# LTC3105_Charger.net
KiCad netlist of a schematic drawn in EAGLE
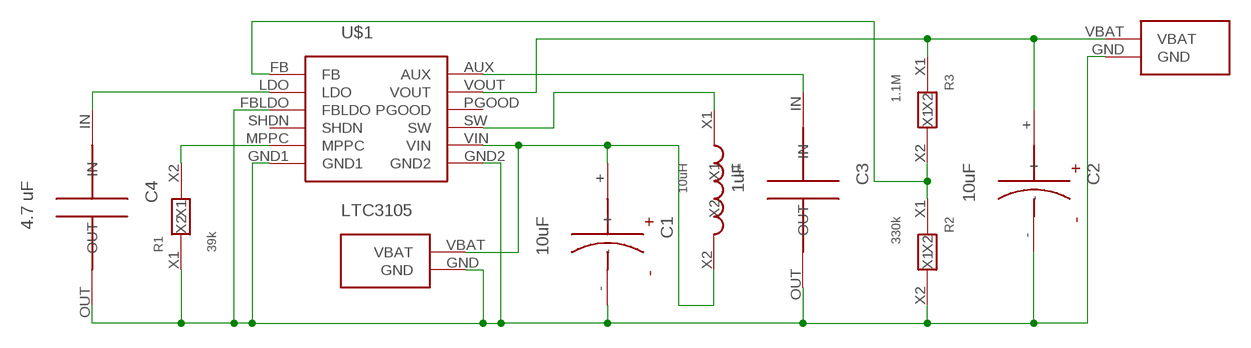
[diagram p0: schematic, sheet 1]

(export (version "E")
  (design (tool "Eeschema 10.0.6"))
  (components
    (comp (ref "C1")
      (value "10uF")
      (footprint "eagle-import:C_ELT_2MM")
      (libsource (lib "eagle-import") (part "C_ELT_2MM"))
    )
    (comp (ref "C2")
      (value "10uF")
      (footprint "eagle-import:C_ELT_2MM")
      (libsource (lib "eagle-import") (part "C_ELT_2MM"))
    )
    (comp (ref "C3")
      (value "1uF")
      (footprint "eagle-import:C_CER_5MM")
      (libsource (lib "eagle-import") (part "C_CER_5MM"))
    )
    (comp (ref "C4")
      (value "4.7 uF")
      (footprint "eagle-import:C_CER_5MM")
      (libsource (lib "eagle-import") (part "C_CER_5MM"))
    )
    (comp (ref "L1")
      (value "10uH")
      (footprint "eagle-import:L_10X3")
      (libsource (lib "eagle-import") (part "L_10X3"))
    )
    (comp (ref "R1")
      (value "39k")
      (footprint "eagle-import:R_6X2")
      (libsource (lib "eagle-import") (part "R_6X2"))
    )
    (comp (ref "R2")
      (value "330k")
      (footprint "eagle-import:R_6X2")
      (libsource (lib "eagle-import") (part "R_6X2"))
    )
    (comp (ref "R3")
      (value "1.1M")
      (footprint "eagle-import:R_6X2")
      (libsource (lib "eagle-import") (part "R_6X2"))
    )
    (comp (ref "U$1")
      (value "LTC3105")
      (footprint "eagle-import:LTC3105")
      (libsource (lib "eagle-import") (part "LTC3105"))
    )
    (comp (ref "U$10")
      (value "BAT_PLUG")
      (footprint "eagle-import:BAT_PLUG")
      (libsource (lib "eagle-import") (part "BAT_PLUG"))
    )
    (comp (ref "U$11")
      (value "BAT_PLUG")
      (footprint "eagle-import:BAT_PLUG")
      (libsource (lib "eagle-import") (part "BAT_PLUG"))
    )
  )
  (nets
    (net (code "1") (name "Net-(C1-Pad+)") (class "Default")
      (node (ref "C1") (pin "+") (pinfunction "+_+") (pintype "bidirectional"))
      (node (ref "L1") (pin "X2") (pinfunction "X2_X2") (pintype "bidirectional"))
      (node (ref "U$1") (pin "VIN") (pinfunction "VIN_VIN") (pintype "bidirectional"))
      (node (ref "U$10") (pin "VBAT") (pinfunction "VBAT_VBAT") (pintype "bidirectional"))
    )
    (net (code "2") (name "Net-(C1-Pad-)") (class "Default")
      (node (ref "C1") (pin "-") (pinfunction "-_-") (pintype "bidirectional"))
      (node (ref "C2") (pin "-") (pinfunction "-_-") (pintype "bidirectional"))
      (node (ref "C3") (pin "OUT") (pinfunction "OUT_OUT") (pintype "bidirectional"))
      (node (ref "C4") (pin "OUT") (pinfunction "OUT_OUT") (pintype "bidirectional"))
      (node (ref "R1") (pin "X1") (pinfunction "X1_X1") (pintype "bidirectional"))
      (node (ref "R2") (pin "X2") (pinfunction "X2_X2") (pintype "bidirectional"))
      (node (ref "U$1") (pin "FBLDO") (pinfunction "FBLDO_FBLDO") (pintype "bidirectional"))
      (node (ref "U$1") (pin "GND1") (pinfunction "GND1_GND1") (pintype "bidirectional"))
      (node (ref "U$1") (pin "GND2") (pinfunction "GND2_GND2") (pintype "bidirectional"))
      (node (ref "U$10") (pin "GND") (pinfunction "GND_GND") (pintype "bidirectional"))
      (node (ref "U$11") (pin "GND") (pinfunction "GND_GND") (pintype "bidirectional"))
    )
    (net (code "3") (name "Net-(C2-Pad+)") (class "Default")
      (node (ref "C2") (pin "+") (pinfunction "+_+") (pintype "bidirectional"))
      (node (ref "R3") (pin "X1") (pinfunction "X1_X1") (pintype "bidirectional"))
      (node (ref "U$1") (pin "VOUT") (pinfunction "VOUT_VOUT") (pintype "bidirectional"))
      (node (ref "U$11") (pin "VBAT") (pinfunction "VBAT_VBAT") (pintype "bidirectional"))
    )
    (net (code "4") (name "Net-(C3-PadIN)") (class "Default")
      (node (ref "C3") (pin "IN") (pinfunction "IN_IN") (pintype "bidirectional"))
      (node (ref "U$1") (pin "AUX") (pinfunction "AUX_AUX") (pintype "bidirectional"))
    )
    (net (code "5") (name "Net-(C4-PadIN)") (class "Default")
      (node (ref "C4") (pin "IN") (pinfunction "IN_IN") (pintype "bidirectional"))
      (node (ref "U$1") (pin "LDO") (pinfunction "LDO_LDO") (pintype "bidirectional"))
    )
    (net (code "6") (name "Net-(L1-PadX1)") (class "Default")
      (node (ref "L1") (pin "X1") (pinfunction "X1_X1") (pintype "bidirectional"))
      (node (ref "U$1") (pin "SW") (pinfunction "SW_SW") (pintype "bidirectional"))
    )
    (net (code "7") (name "Net-(R1-PadX2)") (class "Default")
      (node (ref "R1") (pin "X2") (pinfunction "X2_X2") (pintype "bidirectional"))
      (node (ref "U$1") (pin "MPPC") (pinfunction "MPPC_MPPC") (pintype "bidirectional"))
    )
    (net (code "8") (name "Net-(R2-PadX1)") (class "Default")
      (node (ref "R2") (pin "X1") (pinfunction "X1_X1") (pintype "bidirectional"))
      (node (ref "R3") (pin "X2") (pinfunction "X2_X2") (pintype "bidirectional"))
      (node (ref "U$1") (pin "FB") (pinfunction "FB_FB") (pintype "bidirectional"))
    )
    (net (code "9") (name "unconnected-(U$1-PadPGOOD)") (class "Default")
      (node (ref "U$1") (pin "PGOOD") (pinfunction "PGOOD_PGOOD") (pintype "bidirectional"))
    )
    (net (code "10") (name "unconnected-(U$1-PadSHDN)") (class "Default")
      (node (ref "U$1") (pin "SHDN") (pinfunction "SHDN_SHDN") (pintype "bidirectional"))
    )
  )
)
